# coop_assistant.net
KiCad netlist of a schematic drawn in EAGLE
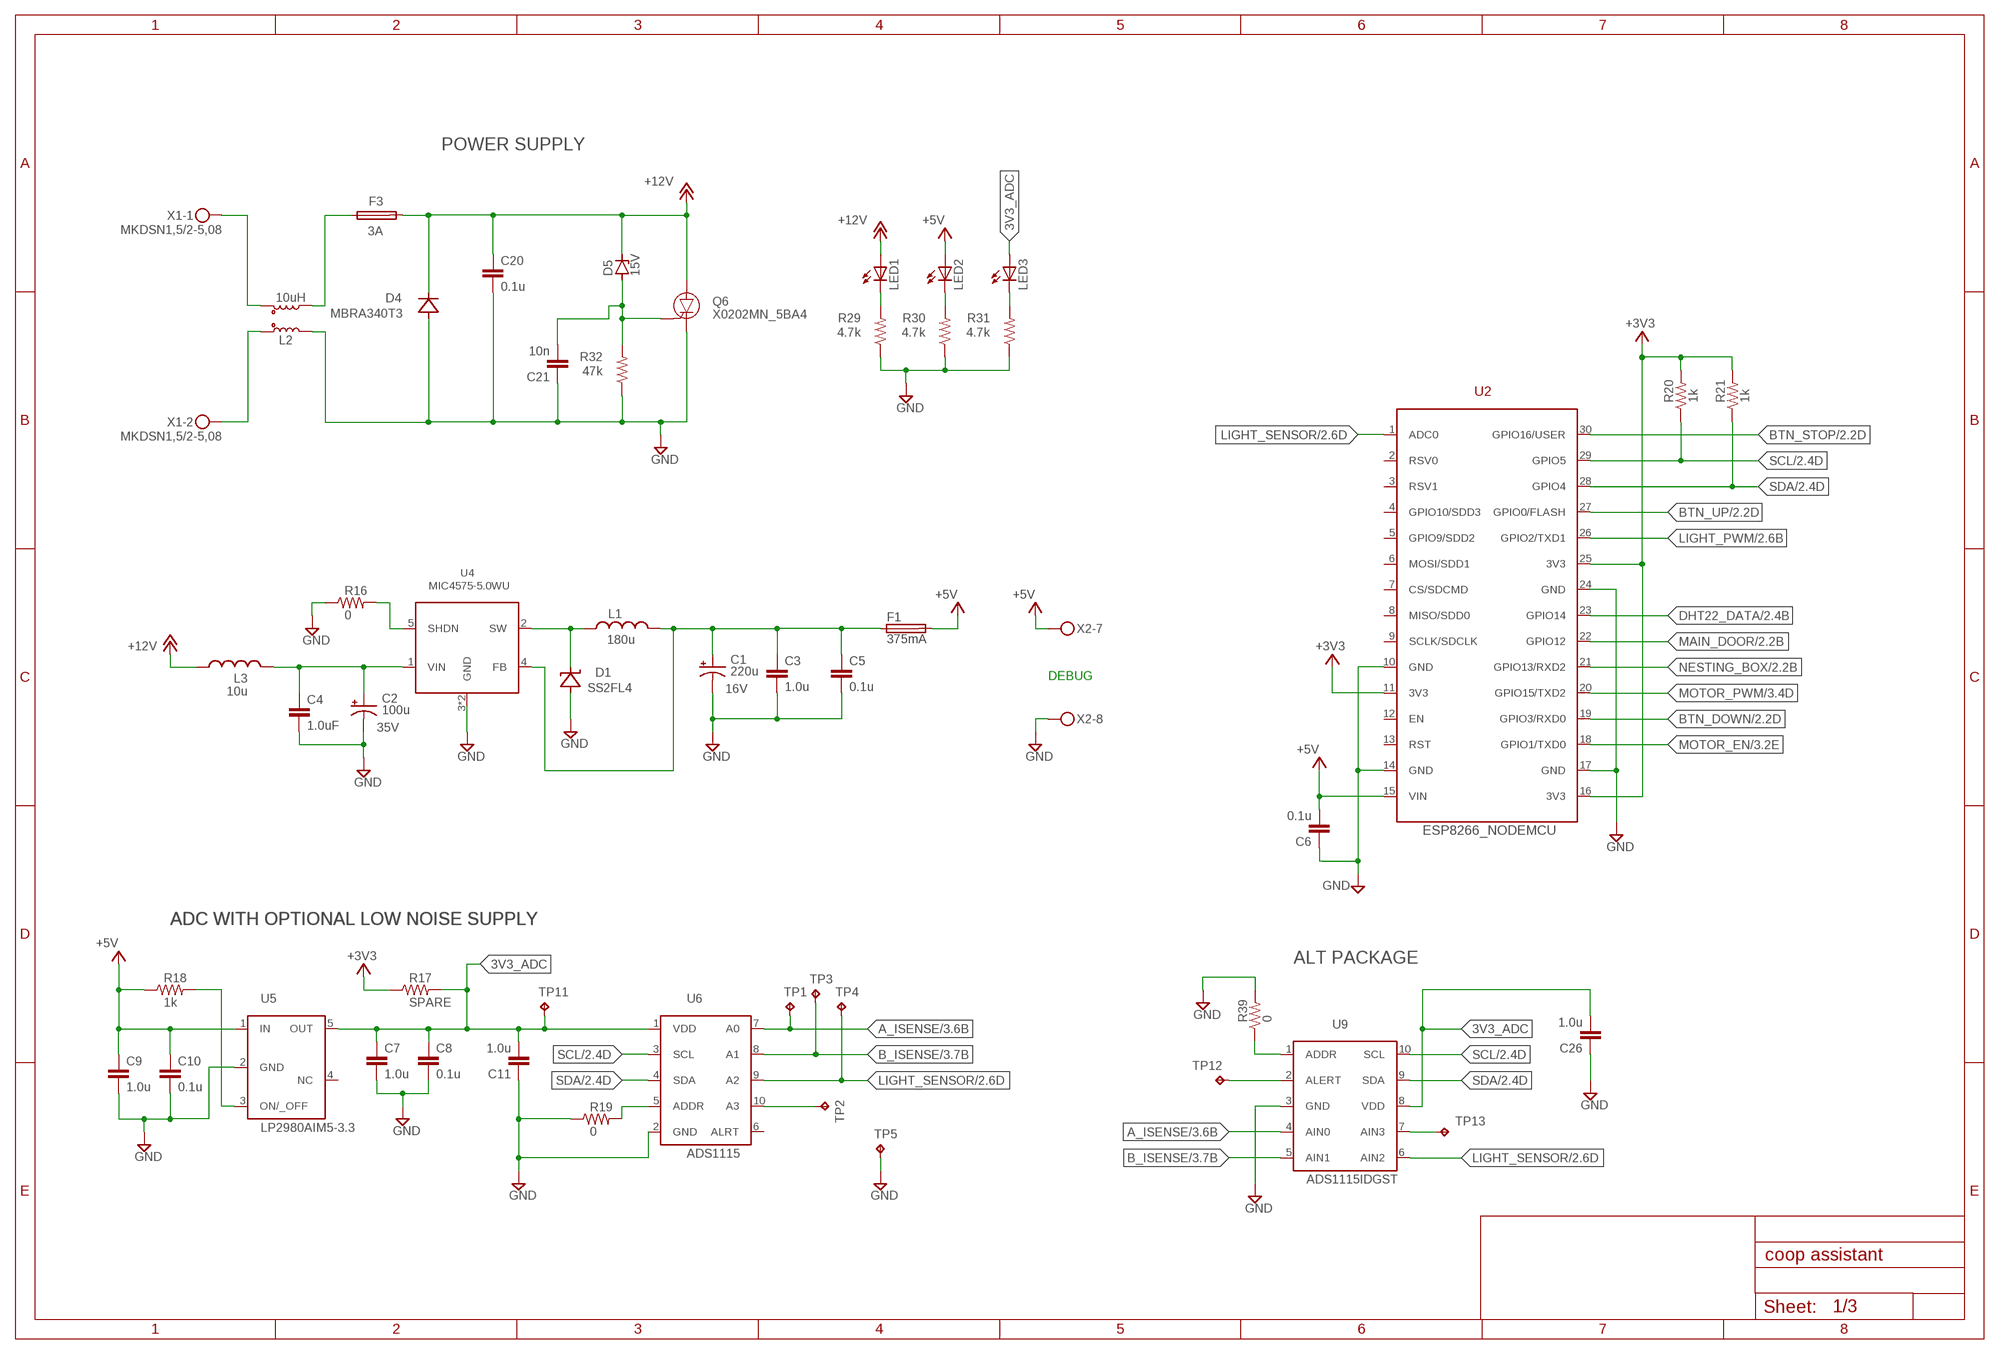
[diagram p0: schematic, sheet 1]
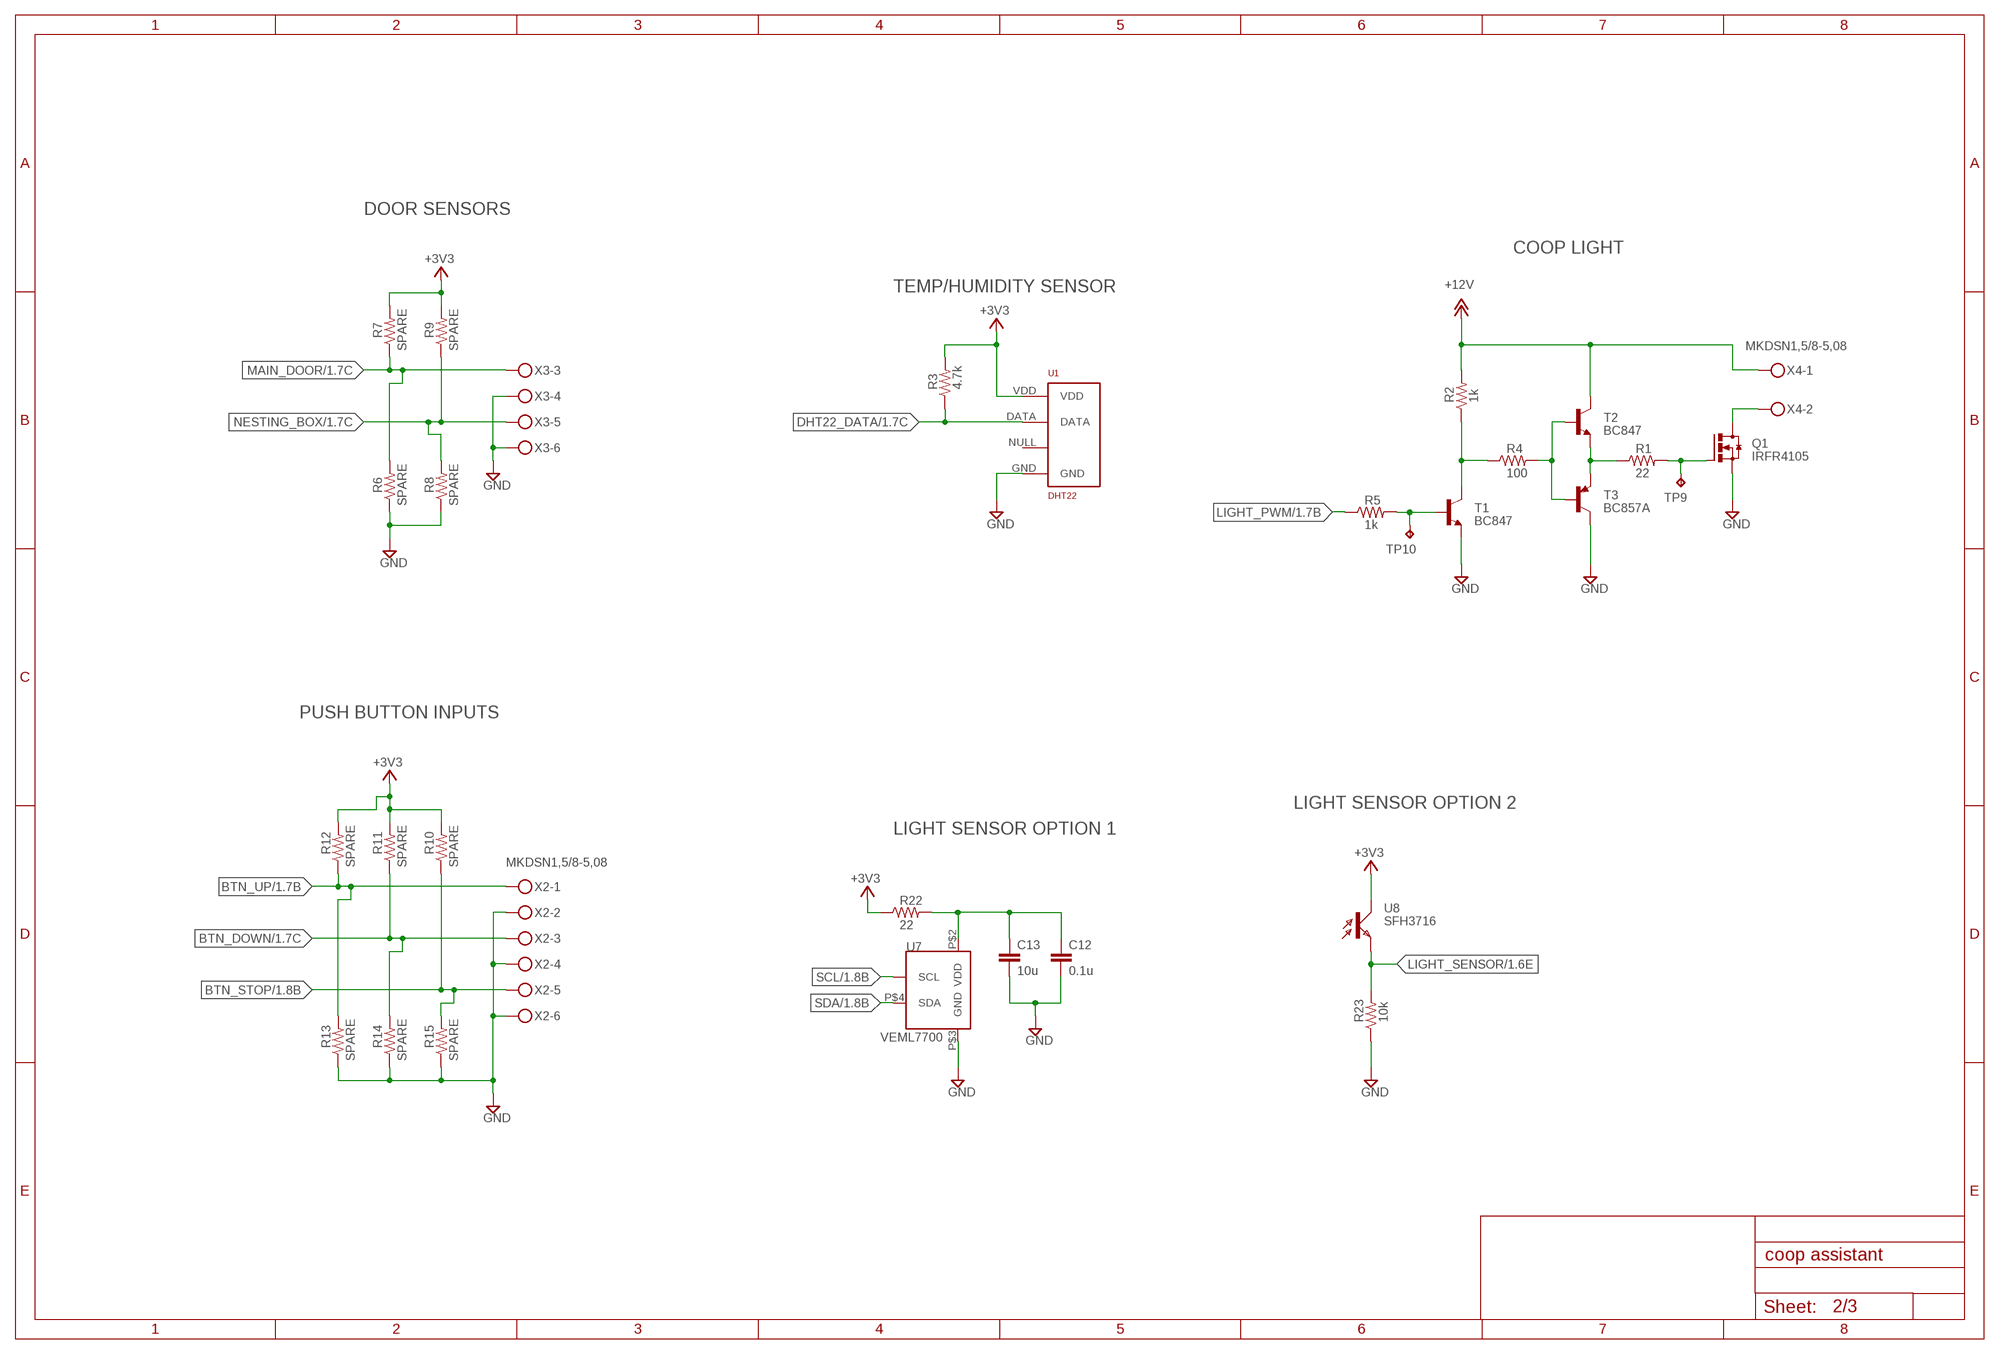
[diagram p1: schematic, sheet 2]
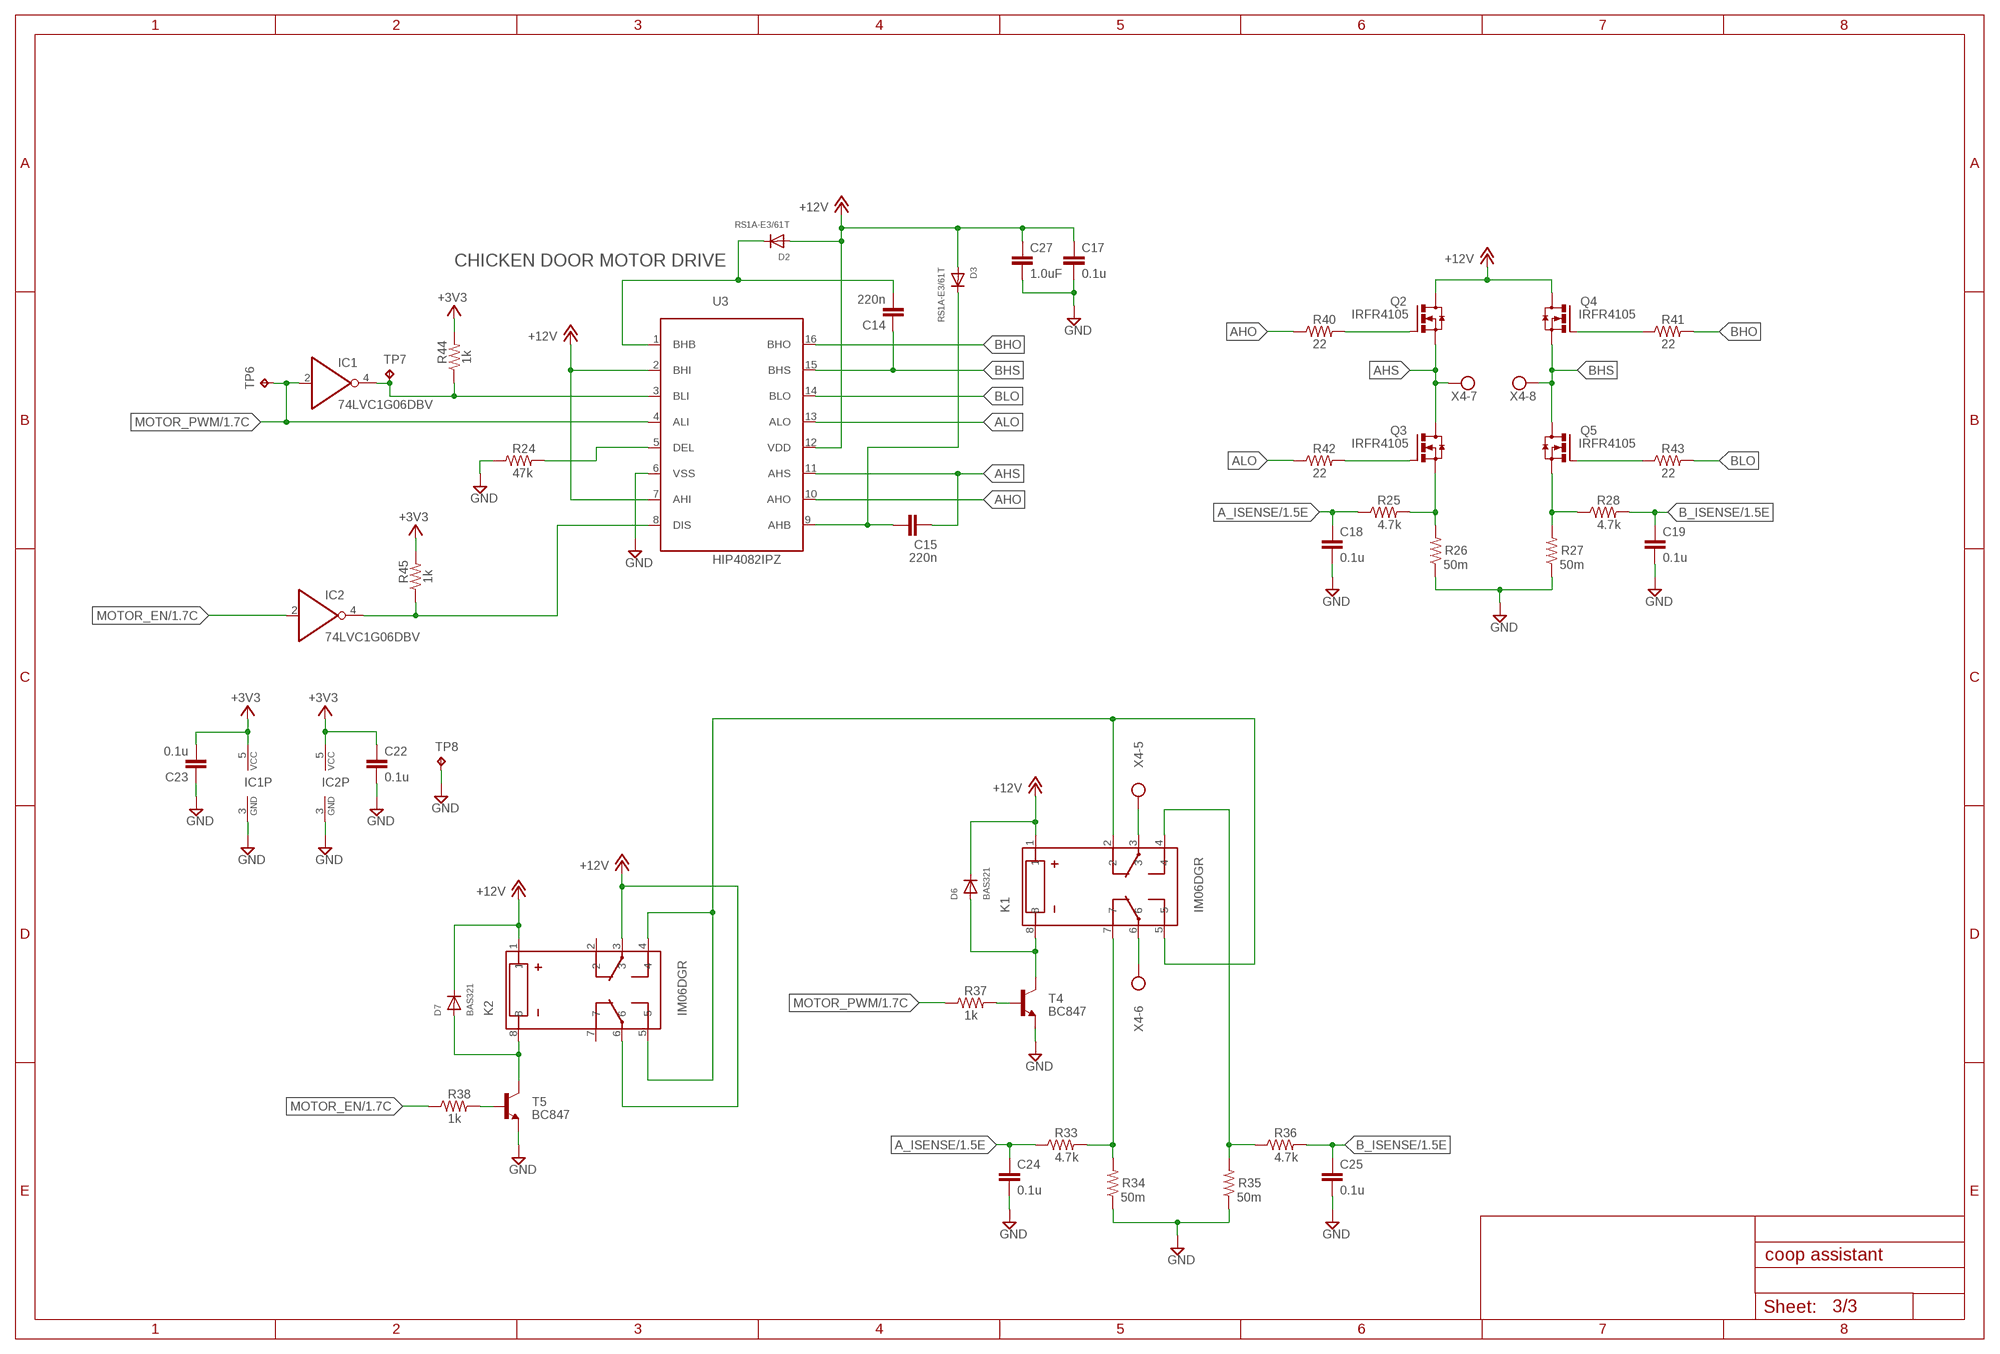
[diagram p2: schematic, sheet 3]

(export (version "E")
  (design (tool "Eeschema 10.0.6"))
  (components
    (comp (ref "C14")
      (value "220n")
      (footprint "eagle-import:0805")
      (libsource (lib "eagle-import") (part "1.0UF-0805-25V-(+80/-20%)"))
    )
    (comp (ref "C15")
      (value "220n")
      (footprint "eagle-import:0805")
      (libsource (lib "eagle-import") (part "1.0UF-0805-25V-(+80/-20%)"))
    )
    (comp (ref "C17")
      (value "0.1u")
      (footprint "eagle-import:0603")
      (libsource (lib "eagle-import") (part "1.0UF-0603-16V-10%"))
    )
    (comp (ref "C18")
      (value "0.1u")
      (footprint "eagle-import:0603")
      (libsource (lib "eagle-import") (part "1.0UF-0603-16V-10%"))
    )
    (comp (ref "C19")
      (value "0.1u")
      (footprint "eagle-import:0603")
      (libsource (lib "eagle-import") (part "1.0UF-0603-16V-10%"))
    )
    (comp (ref "C22")
      (value "0.1u")
      (footprint "eagle-import:0603")
      (libsource (lib "eagle-import") (part "1.0UF-0603-16V-10%"))
    )
    (comp (ref "C23")
      (value "0.1u")
      (footprint "eagle-import:0603")
      (libsource (lib "eagle-import") (part "1.0UF-0603-16V-10%"))
    )
    (comp (ref "C24")
      (value "0.1u")
      (footprint "eagle-import:0603")
      (libsource (lib "eagle-import") (part "1.0UF-0603-16V-10%"))
    )
    (comp (ref "C25")
      (value "0.1u")
      (footprint "eagle-import:0603")
      (libsource (lib "eagle-import") (part "1.0UF-0603-16V-10%"))
    )
    (comp (ref "C27")
      (value "1.0uF")
      (footprint "eagle-import:0805")
      (libsource (lib "eagle-import") (part "1.0UF-0805-25V-10%"))
    )
    (comp (ref "D2")
      (value "RS1A-E3/61T")
      (footprint "eagle-import:SMADIODE")
      (libsource (lib "eagle-import") (part "DIODESMA"))
    )
    (comp (ref "D3")
      (value "RS1A-E3/61T")
      (footprint "eagle-import:SMADIODE")
      (libsource (lib "eagle-import") (part "DIODESMA"))
    )
    (comp (ref "D6")
      (value "BAS321")
      (footprint "eagle-import:SOD-323F")
      (libsource (lib "eagle-import") (part "DIODESOD-323F"))
    )
    (comp (ref "D7")
      (value "BAS321")
      (footprint "eagle-import:SOD-323F")
      (libsource (lib "eagle-import") (part "DIODESOD-323F"))
    )
    (comp (ref "IC1")
      (value "74LVC1G06DBV")
      (footprint "eagle-import:SOT23-5")
      (libsource (lib "eagle-import") (part "741G06DBVLVC"))
    )
    (comp (ref "IC2")
      (value "74LVC1G06DBV")
      (footprint "eagle-import:SOT23-5")
      (libsource (lib "eagle-import") (part "741G06DBVLVC"))
    )
    (comp (ref "K1")
      (value "IM06DGR")
      (footprint "eagle-import:AXICOM_IM")
      (libsource (lib "eagle-import") (part "IM06DGR"))
    )
    (comp (ref "K2")
      (value "IM06DGR")
      (footprint "eagle-import:AXICOM_IM")
      (libsource (lib "eagle-import") (part "IM06DGR"))
    )
    (comp (ref "Q2")
      (value "IRFR4105")
      (footprint "eagle-import:TO252")
      (libsource (lib "eagle-import") (part "IRFR4105"))
    )
    (comp (ref "Q3")
      (value "IRFR4105")
      (footprint "eagle-import:TO252")
      (libsource (lib "eagle-import") (part "IRFR4105"))
    )
    (comp (ref "Q4")
      (value "IRFR4105")
      (footprint "eagle-import:TO252")
      (libsource (lib "eagle-import") (part "IRFR4105"))
    )
    (comp (ref "Q5")
      (value "IRFR4105")
      (footprint "eagle-import:TO252")
      (libsource (lib "eagle-import") (part "IRFR4105"))
    )
    (comp (ref "R24")
      (value "47k")
      (footprint "eagle-import:R0805")
      (libsource (lib "eagle-import") (part "R-US_R0805"))
    )
    (comp (ref "R25")
      (value "4.7k")
      (footprint "eagle-import:R0805")
      (libsource (lib "eagle-import") (part "R-US_R0805"))
    )
    (comp (ref "R26")
      (value "50m")
      (footprint "eagle-import:R2512")
      (libsource (lib "eagle-import") (part "R-US_R2512"))
    )
    (comp (ref "R27")
      (value "50m")
      (footprint "eagle-import:R2512")
      (libsource (lib "eagle-import") (part "R-US_R2512"))
    )
    (comp (ref "R28")
      (value "4.7k")
      (footprint "eagle-import:R0805")
      (libsource (lib "eagle-import") (part "R-US_R0805"))
    )
    (comp (ref "R33")
      (value "4.7k")
      (footprint "eagle-import:R0805")
      (libsource (lib "eagle-import") (part "R-US_R0805"))
    )
    (comp (ref "R34")
      (value "50m")
      (footprint "eagle-import:R2512")
      (libsource (lib "eagle-import") (part "R-US_R2512"))
    )
    (comp (ref "R35")
      (value "50m")
      (footprint "eagle-import:R2512")
      (libsource (lib "eagle-import") (part "R-US_R2512"))
    )
    (comp (ref "R36")
      (value "4.7k")
      (footprint "eagle-import:R0805")
      (libsource (lib "eagle-import") (part "R-US_R0805"))
    )
    (comp (ref "R37")
      (value "1k")
      (footprint "eagle-import:R0805")
      (libsource (lib "eagle-import") (part "R-US_R0805"))
    )
    (comp (ref "R38")
      (value "1k")
      (footprint "eagle-import:R0805")
      (libsource (lib "eagle-import") (part "R-US_R0805"))
    )
    (comp (ref "R40")
      (value "22")
      (footprint "eagle-import:R0805")
      (libsource (lib "eagle-import") (part "R-US_R0805"))
    )
    (comp (ref "R41")
      (value "22")
      (footprint "eagle-import:R0805")
      (libsource (lib "eagle-import") (part "R-US_R0805"))
    )
    (comp (ref "R42")
      (value "22")
      (footprint "eagle-import:R0805")
      (libsource (lib "eagle-import") (part "R-US_R0805"))
    )
    (comp (ref "R43")
      (value "22")
      (footprint "eagle-import:R0805")
      (libsource (lib "eagle-import") (part "R-US_R0805"))
    )
    (comp (ref "R44")
      (value "1k")
      (footprint "eagle-import:R0805")
      (libsource (lib "eagle-import") (part "R-US_R0805"))
    )
    (comp (ref "R45")
      (value "1k")
      (footprint "eagle-import:R0805")
      (libsource (lib "eagle-import") (part "R-US_R0805"))
    )
    (comp (ref "T4")
      (value "BC847")
      (footprint "eagle-import:SOT23")
      (libsource (lib "eagle-import") (part "BC847"))
    )
    (comp (ref "T5")
      (value "BC847")
      (footprint "eagle-import:SOT23")
      (libsource (lib "eagle-import") (part "BC847"))
    )
    (comp (ref "TP6")
      (value "TPTP15SQ")
      (footprint "eagle-import:TP15SQ")
      (libsource (lib "eagle-import") (part "TPTP15SQ"))
    )
    (comp (ref "TP7")
      (value "TPTP15SQ")
      (footprint "eagle-import:TP15SQ")
      (libsource (lib "eagle-import") (part "TPTP15SQ"))
    )
    (comp (ref "TP8")
      (value "TPTP15SQ")
      (footprint "eagle-import:TP15SQ")
      (libsource (lib "eagle-import") (part "TPTP15SQ"))
    )
    (comp (ref "U3")
      (value "HIP4082IPZ")
      (footprint "eagle-import:DIP762W53P254L1969H508Q16B")
      (libsource (lib "eagle-import") (part "HIP4082IPZ"))
    )
    (comp (ref "X4")
      (value "MKDSN1,5/8-5,08")
      (footprint "eagle-import:MKDSN1,5_8-5,08")
      (libsource (lib "eagle-import") (part "MKDSN1,5/8-5,08"))
    )
    (comp (ref "C1")
      (value "220u")
      (footprint "eagle-import:CAPPRD250W50D630H800B")
      (fields (field (name "VOLTAGE") "16V"))
      (libsource (lib "eagle-import") (part "CPOLRAD6.3X8"))
    )
    (comp (ref "C2")
      (value "100u")
      (footprint "eagle-import:CAPPRD350W60D800H1200B")
      (fields (field (name "VOLTAGE") "35V"))
      (libsource (lib "eagle-import") (part "CPOLRAD8X12"))
    )
    (comp (ref "C3")
      (value "1.0u")
      (footprint "eagle-import:0805")
      (libsource (lib "eagle-import") (part "1.0UF-0805-25V-10%"))
    )
    (comp (ref "C4")
      (value "1.0uF")
      (footprint "eagle-import:0805")
      (libsource (lib "eagle-import") (part "1.0UF-0805-25V-10%"))
    )
    (comp (ref "C5")
      (value "0.1u")
      (footprint "eagle-import:0603")
      (libsource (lib "eagle-import") (part "1.0UF-0603-16V-10%"))
    )
    (comp (ref "C6")
      (value "0.1u")
      (footprint "eagle-import:0603")
      (libsource (lib "eagle-import") (part "1.0UF-0603-16V-10%"))
    )
    (comp (ref "C7")
      (value "1.0u")
      (footprint "eagle-import:0805")
      (libsource (lib "eagle-import") (part "1.0UF-0805-25V-10%"))
    )
    (comp (ref "C8")
      (value "0.1u")
      (footprint "eagle-import:0603")
      (libsource (lib "eagle-import") (part "1.0UF-0603-16V-10%"))
    )
    (comp (ref "C9")
      (value "1.0u")
      (footprint "eagle-import:0805")
      (libsource (lib "eagle-import") (part "1.0UF-0805-25V-10%"))
    )
    (comp (ref "C10")
      (value "0.1u")
      (footprint "eagle-import:0603")
      (libsource (lib "eagle-import") (part "1.0UF-0603-16V-10%"))
    )
    (comp (ref "C11")
      (value "1.0u")
      (footprint "eagle-import:0805")
      (libsource (lib "eagle-import") (part "1.0UF-0805-25V-10%"))
    )
    (comp (ref "C20")
      (value "0.1u")
      (footprint "eagle-import:C0805")
      (libsource (lib "eagle-import") (part "C-EUC0805"))
    )
    (comp (ref "C21")
      (value "10n")
      (footprint "eagle-import:C0805")
      (libsource (lib "eagle-import") (part "C-EUC0805"))
    )
    (comp (ref "C26")
      (value "1.0u")
      (footprint "eagle-import:0805")
      (libsource (lib "eagle-import") (part "1.0UF-0805-25V-10%"))
    )
    (comp (ref "D1")
      (value "SS2FL4")
      (footprint "eagle-import:SMF")
      (libsource (lib "eagle-import") (part "SS2FL4"))
    )
    (comp (ref "D4")
      (value "MBRA340T3")
      (footprint "eagle-import:SMA")
      (libsource (lib "eagle-import") (part "MBRA340T3"))
    )
    (comp (ref "D5")
      (value "15V")
      (footprint "eagle-import:SOT23")
      (libsource (lib "eagle-import") (part "ZENER-DIODESOT23"))
    )
    (comp (ref "F1")
      (value "375mA")
      (footprint "eagle-import:0603")
      (libsource (lib "eagle-import") (part "494SERIESFUSE"))
    )
    (comp (ref "F3")
      (value "3A")
      (footprint "eagle-import:FUSM9750X381N")
      (libsource (lib "eagle-import") (part "154_OMNIBLOKF154"))
    )
    (comp (ref "L1")
      (value "180u")
      (footprint "eagle-import:INDM120120X780N")
      (libsource (lib "eagle-import") (part "MSS1278"))
    )
    (comp (ref "L2")
      (value "10uH")
      (footprint "eagle-import:COILCRAFT_MSD1260")
      (libsource (lib "eagle-import") (part "COILCRAFT_MSD1260"))
    )
    (comp (ref "L3")
      (value "10u")
      (footprint "eagle-import:INDM120120X780N")
      (libsource (lib "eagle-import") (part "MSS1278"))
    )
    (comp (ref "LED1")
      (value "LEDCHIP-LED0805")
      (footprint "eagle-import:CHIP-LED0805")
      (libsource (lib "eagle-import") (part "LEDCHIP-LED0805"))
    )
    (comp (ref "LED2")
      (value "LEDCHIP-LED0805")
      (footprint "eagle-import:CHIP-LED0805")
      (libsource (lib "eagle-import") (part "LEDCHIP-LED0805"))
    )
    (comp (ref "LED3")
      (value "LEDCHIP-LED0805")
      (footprint "eagle-import:CHIP-LED0805")
      (libsource (lib "eagle-import") (part "LEDCHIP-LED0805"))
    )
    (comp (ref "Q6")
      (value "X0202MN_5BA4")
      (footprint "eagle-import:SOT-223")
      (fields
        (field (name "DIGIKEY_PARTNO") "497-2532-2-ND")
        (field (name "MANUFACTURER") "STMicroelectronics")
        (field (name "MPN") "X0202MN 5BA4")
        (field (name "CREATED_BY") "PCBLayout.com")
      )
      (libsource (lib "eagle-import") (part "X0202MN_5BA4"))
    )
    (comp (ref "R16")
      (value "0")
      (footprint "eagle-import:R0805")
      (libsource (lib "eagle-import") (part "R-US_R0805"))
    )
    (comp (ref "R17")
      (value "SPARE")
      (footprint "eagle-import:R0805")
      (libsource (lib "eagle-import") (part "R-US_R0805"))
    )
    (comp (ref "R18")
      (value "1k")
      (footprint "eagle-import:R0805")
      (libsource (lib "eagle-import") (part "R-US_R0805"))
    )
    (comp (ref "R19")
      (value "0")
      (footprint "eagle-import:R0805")
      (libsource (lib "eagle-import") (part "R-US_R0805"))
    )
    (comp (ref "R20")
      (value "1k")
      (footprint "eagle-import:R0805")
      (libsource (lib "eagle-import") (part "R-US_R0805"))
    )
    (comp (ref "R21")
      (value "1k")
      (footprint "eagle-import:R0805")
      (libsource (lib "eagle-import") (part "R-US_R0805"))
    )
    (comp (ref "R29")
      (value "4.7k")
      (footprint "eagle-import:R0805")
      (libsource (lib "eagle-import") (part "R-US_R0805"))
    )
    (comp (ref "R30")
      (value "4.7k")
      (footprint "eagle-import:R0805")
      (libsource (lib "eagle-import") (part "R-US_R0805"))
    )
    (comp (ref "R31")
      (value "4.7k")
      (footprint "eagle-import:R0805")
      (libsource (lib "eagle-import") (part "R-US_R0805"))
    )
    (comp (ref "R32")
      (value "47k")
      (footprint "eagle-import:R0805")
      (libsource (lib "eagle-import") (part "R-US_R0805"))
    )
    (comp (ref "R39")
      (value "0")
      (footprint "eagle-import:R0805")
      (libsource (lib "eagle-import") (part "R-US_R0805"))
    )
    (comp (ref "TP1")
      (value "TPTP15SQ")
      (footprint "eagle-import:TP15SQ")
      (libsource (lib "eagle-import") (part "TPTP15SQ"))
    )
    (comp (ref "TP2")
      (value "TPTP15SQ")
      (footprint "eagle-import:TP15SQ")
      (libsource (lib "eagle-import") (part "TPTP15SQ"))
    )
    (comp (ref "TP3")
      (value "TPTP15SQ")
      (footprint "eagle-import:TP15SQ")
      (libsource (lib "eagle-import") (part "TPTP15SQ"))
    )
    (comp (ref "TP4")
      (value "TPTP15SQ")
      (footprint "eagle-import:TP15SQ")
      (libsource (lib "eagle-import") (part "TPTP15SQ"))
    )
    (comp (ref "TP5")
      (value "TPTP15SQ")
      (footprint "eagle-import:TP15SQ")
      (libsource (lib "eagle-import") (part "TPTP15SQ"))
    )
    (comp (ref "TP11")
      (value "TPTP15SQ")
      (footprint "eagle-import:TP15SQ")
      (libsource (lib "eagle-import") (part "TPTP15SQ"))
    )
    (comp (ref "TP12")
      (value "TPTP15SQ")
      (footprint "eagle-import:TP15SQ")
      (libsource (lib "eagle-import") (part "TPTP15SQ"))
    )
    (comp (ref "TP13")
      (value "TPTP15SQ")
      (footprint "eagle-import:TP15SQ")
      (libsource (lib "eagle-import") (part "TPTP15SQ"))
    )
    (comp (ref "U2")
      (value "ESP8266_NODEMCU")
      (footprint "eagle-import:NODEMCUESP8266")
      (libsource (lib "eagle-import") (part "ESP8266_NODEMCU"))
    )
    (comp (ref "U4")
      (value "MIC4575-5.0WU")
      (footprint "eagle-import:TO263-5")
      (libsource (lib "eagle-import") (part "MIC4575-5.0WU"))
    )
    (comp (ref "U5")
      (value "LP2980AIM5-3.3")
      (footprint "eagle-import:SOT23-5")
      (libsource (lib "eagle-import") (part "LP2980AIM5-3.3"))
    )
    (comp (ref "U6")
      (value "ADS1115")
      (footprint "eagle-import:HDRV10W64P254_1X10_2800X508X838B")
      (libsource (lib "eagle-import") (part "ADS1115"))
    )
    (comp (ref "U9")
      (value "ADS1115IDGST")
      (footprint "eagle-import:10VSSOP")
      (libsource (lib "eagle-import") (part "ADS1115IDGST"))
    )
    (comp (ref "X1")
      (value "MKDSN1,5/2-5,08")
      (footprint "eagle-import:MKDSN1,5_2-5,08")
      (libsource (lib "eagle-import") (part "MKDSN1,5/2-5,08"))
    )
    (comp (ref "X2")
      (value "MKDSN1,5/8-5,08")
      (footprint "eagle-import:MKDSN1,5_8-5,08")
      (libsource (lib "eagle-import") (part "MKDSN1,5/8-5,08"))
    )
    (comp (ref "C12")
      (value "0.1u")
      (footprint "eagle-import:0603")
      (libsource (lib "eagle-import") (part "1.0UF-0603-16V-10%"))
    )
    (comp (ref "C13")
      (value "10u")
      (footprint "eagle-import:0805")
      (libsource (lib "eagle-import") (part "1.0UF-0805-25V-(+80/-20%)"))
    )
    (comp (ref "Q1")
      (value "IRFR4105")
      (footprint "eagle-import:TO252")
      (libsource (lib "eagle-import") (part "IRFR4105"))
    )
    (comp (ref "R1")
      (value "22")
      (footprint "eagle-import:R0805")
      (libsource (lib "eagle-import") (part "R-US_R0805"))
    )
    (comp (ref "R2")
      (value "1k")
      (footprint "eagle-import:R0805")
      (libsource (lib "eagle-import") (part "R-US_R0805"))
    )
    (comp (ref "R3")
      (value "4.7k")
      (footprint "eagle-import:R0805")
      (libsource (lib "eagle-import") (part "R-US_R0805"))
    )
    (comp (ref "R4")
      (value "100")
      (footprint "eagle-import:R0805")
      (libsource (lib "eagle-import") (part "R-US_R0805"))
    )
    (comp (ref "R5")
      (value "1k")
      (footprint "eagle-import:R0805")
      (libsource (lib "eagle-import") (part "R-US_R0805"))
    )
    (comp (ref "R6")
      (value "SPARE")
      (footprint "eagle-import:R0805")
      (libsource (lib "eagle-import") (part "R-US_R0805"))
    )
    (comp (ref "R7")
      (value "SPARE")
      (footprint "eagle-import:R0805")
      (libsource (lib "eagle-import") (part "R-US_R0805"))
    )
    (comp (ref "R8")
      (value "SPARE")
      (footprint "eagle-import:R0805")
      (libsource (lib "eagle-import") (part "R-US_R0805"))
    )
    (comp (ref "R9")
      (value "SPARE")
      (footprint "eagle-import:R0805")
      (libsource (lib "eagle-import") (part "R-US_R0805"))
    )
    (comp (ref "R10")
      (value "SPARE")
      (footprint "eagle-import:R0805")
      (libsource (lib "eagle-import") (part "R-US_R0805"))
    )
    (comp (ref "R11")
      (value "SPARE")
      (footprint "eagle-import:R0805")
      (libsource (lib "eagle-import") (part "R-US_R0805"))
    )
    (comp (ref "R12")
      (value "SPARE")
      (footprint "eagle-import:R0805")
      (libsource (lib "eagle-import") (part "R-US_R0805"))
    )
    (comp (ref "R13")
      (value "SPARE")
      (footprint "eagle-import:R0805")
      (libsource (lib "eagle-import") (part "R-US_R0805"))
    )
    (comp (ref "R14")
      (value "SPARE")
      (footprint "eagle-import:R0805")
      (libsource (lib "eagle-import") (part "R-US_R0805"))
    )
    (comp (ref "R15")
      (value "SPARE")
      (footprint "eagle-import:R0805")
      (libsource (lib "eagle-import") (part "R-US_R0805"))
    )
    (comp (ref "R22")
      (value "22")
      (footprint "eagle-import:R0805")
      (libsource (lib "eagle-import") (part "R-US_R0805"))
    )
    (comp (ref "R23")
      (value "10k")
      (footprint "eagle-import:R0805")
      (libsource (lib "eagle-import") (part "R-US_R0805"))
    )
    (comp (ref "T1")
      (value "BC847")
      (footprint "eagle-import:SOT23")
      (libsource (lib "eagle-import") (part "BC847"))
    )
    (comp (ref "T2")
      (value "BC847")
      (footprint "eagle-import:SOT23")
      (libsource (lib "eagle-import") (part "BC847"))
    )
    (comp (ref "T3")
      (value "BC857A")
      (footprint "eagle-import:SOT23-BEC")
      (libsource (lib "eagle-import") (part "BC857A"))
    )
    (comp (ref "TP9")
      (value "TPTP15SQ")
      (footprint "eagle-import:TP15SQ")
      (libsource (lib "eagle-import") (part "TPTP15SQ"))
    )
    (comp (ref "TP10")
      (value "TPTP15SQ")
      (footprint "eagle-import:TP15SQ")
      (libsource (lib "eagle-import") (part "TPTP15SQ"))
    )
    (comp (ref "U1")
      (value "DHT22")
      (footprint "eagle-import:RHT03_DHT-22_RA")
      (libsource (lib "eagle-import") (part "RHT03_DHT-22_AM2302RA"))
    )
    (comp (ref "U7")
      (value "VEML7700")
      (footprint "eagle-import:VEML7700")
      (libsource (lib "eagle-import") (part "VEML7700"))
    )
    (comp (ref "U8")
      (value "SFH3716")
      (footprint "eagle-import:0805")
      (libsource (lib "eagle-import") (part "SFH3716"))
    )
    (comp (ref "X3")
      (value "MKDSN1,5/8-5,08")
      (footprint "eagle-import:MKDSN1,5_8-5,08")
      (libsource (lib "eagle-import") (part "MKDSN1,5/8-5,08"))
    )
  )
  (nets
    (net (code "1") (name "+3V3") (class "Default")
      (node (ref "C22") (pin "1") (pinfunction "1_1") (pintype "passive"))
      (node (ref "C23") (pin "2") (pinfunction "2_2") (pintype "passive"))
      (node (ref "IC1") (pin "5") (pinfunction "VCC_5") (pintype "power_in"))
      (node (ref "IC2") (pin "5") (pinfunction "VCC_5") (pintype "power_in"))
      (node (ref "R10") (pin "2") (pinfunction "2_2") (pintype "passive"))
      (node (ref "R11") (pin "2") (pinfunction "2_2") (pintype "passive"))
      (node (ref "R12") (pin "2") (pinfunction "2_2") (pintype "passive"))
      (node (ref "R17") (pin "1") (pinfunction "1_1") (pintype "passive"))
      (node (ref "R20") (pin "2") (pinfunction "2_2") (pintype "passive"))
      (node (ref "R21") (pin "2") (pinfunction "2_2") (pintype "passive"))
      (node (ref "R22") (pin "1") (pinfunction "1_1") (pintype "passive"))
      (node (ref "R3") (pin "2") (pinfunction "2_2") (pintype "passive"))
      (node (ref "R44") (pin "2") (pinfunction "2_2") (pintype "passive"))
      (node (ref "R45") (pin "2") (pinfunction "2_2") (pintype "passive"))
      (node (ref "R7") (pin "2") (pinfunction "2_2") (pintype "passive"))
      (node (ref "R9") (pin "2") (pinfunction "2_2") (pintype "passive"))
      (node (ref "U1") (pin "VDD") (pinfunction "VDD_VDD") (pintype "power_in"))
      (node (ref "U2") (pin "11") (pinfunction "3V3_11") (pintype "power_in"))
      (node (ref "U2") (pin "16") (pinfunction "3V3_16") (pintype "power_in"))
      (node (ref "U2") (pin "25") (pinfunction "3V3_25") (pintype "power_in"))
      (node (ref "U8") (pin "1") (pinfunction "C_1") (pintype "passive"))
    )
    (net (code "2") (name "+5V") (class "Default")
      (node (ref "C10") (pin "1") (pinfunction "1_1") (pintype "passive"))
      (node (ref "C6") (pin "2") (pinfunction "2_2") (pintype "passive"))
      (node (ref "C9") (pin "1") (pinfunction "1_1") (pintype "passive"))
      (node (ref "F1") (pin "2") (pinfunction "2_2") (pintype "passive"))
      (node (ref "LED2") (pin "A") (pinfunction "A_A") (pintype "passive"))
      (node (ref "R18") (pin "1") (pinfunction "1_1") (pintype "passive"))
      (node (ref "U2") (pin "15") (pinfunction "VIN_15") (pintype "power_in"))
      (node (ref "U5") (pin "1") (pinfunction "IN_1") (pintype "power_in"))
      (node (ref "X2") (pin "7") (pinfunction "KL_7") (pintype "passive"))
    )
    (net (code "3") (name "+12V") (class "Default")
      (node (ref "C17") (pin "1") (pinfunction "1_1") (pintype "passive"))
      (node (ref "C20") (pin "1") (pinfunction "1_1") (pintype "passive"))
      (node (ref "C27") (pin "1") (pinfunction "1_1") (pintype "passive"))
      (node (ref "D2") (pin "A") (pinfunction "A_A") (pintype "passive"))
      (node (ref "D3") (pin "A") (pinfunction "A_A") (pintype "passive"))
      (node (ref "D4") (pin "C") (pinfunction "C_C") (pintype "passive"))
      (node (ref "D5") (pin "3") (pinfunction "C_3") (pintype "passive"))
      (node (ref "D6") (pin "C") (pinfunction "C_C") (pintype "passive"))
      (node (ref "D7") (pin "C") (pinfunction "C_C") (pintype "passive"))
      (node (ref "F3") (pin "2") (pinfunction "2_2") (pintype "passive"))
      (node (ref "K1") (pin "1") (pinfunction "1_1") (pintype "bidirectional"))
      (node (ref "K2") (pin "1") (pinfunction "1_1") (pintype "bidirectional"))
      (node (ref "K2") (pin "3") (pinfunction "3_3") (pintype "bidirectional"))
      (node (ref "K2") (pin "6") (pinfunction "6_6") (pintype "bidirectional"))
      (node (ref "L3") (pin "1") (pinfunction "1_1") (pintype "passive"))
      (node (ref "LED1") (pin "A") (pinfunction "A_A") (pintype "passive"))
      (node (ref "Q2") (pin "3") (pinfunction "D_3") (pintype "passive"))
      (node (ref "Q4") (pin "3") (pinfunction "D_3") (pintype "passive"))
      (node (ref "Q6") (pin "A") (pinfunction "A_A") (pintype "passive"))
      (node (ref "Q6") (pin "A1") (pinfunction "A_A1") (pintype "passive"))
      (node (ref "R2") (pin "2") (pinfunction "2_2") (pintype "passive"))
      (node (ref "T2") (pin "3") (pinfunction "C_3") (pintype "passive"))
      (node (ref "U3") (pin "12") (pinfunction "VDD_12") (pintype "power_in"))
      (node (ref "U3") (pin "2") (pinfunction "BHI_2") (pintype "bidirectional"))
      (node (ref "U3") (pin "7") (pinfunction "AHI_7") (pintype "bidirectional"))
      (node (ref "X4") (pin "1") (pinfunction "KL_1") (pintype "passive"))
    )
    (net (code "4") (name "3V3_ADC") (class "Default")
      (node (ref "C11") (pin "2") (pinfunction "2_2") (pintype "passive"))
      (node (ref "C26") (pin "2") (pinfunction "2_2") (pintype "passive"))
      (node (ref "C7") (pin "1") (pinfunction "1_1") (pintype "passive"))
      (node (ref "C8") (pin "1") (pinfunction "1_1") (pintype "passive"))
      (node (ref "LED3") (pin "A") (pinfunction "A_A") (pintype "passive"))
      (node (ref "R17") (pin "2") (pinfunction "2_2") (pintype "passive"))
      (node (ref "TP11") (pin "TP") (pinfunction "TP_TP") (pintype "input"))
      (node (ref "U5") (pin "5") (pinfunction "OUT_5") (pintype "power_in"))
      (node (ref "U6") (pin "1") (pinfunction "VDD_1") (pintype "power_in"))
      (node (ref "U9") (pin "8") (pinfunction "VDD_8") (pintype "power_in"))
    )
    (net (code "5") (name "AHO") (class "Default")
      (node (ref "R40") (pin "1") (pinfunction "1_1") (pintype "passive"))
      (node (ref "U3") (pin "10") (pinfunction "AHO_10") (pintype "bidirectional"))
    )
    (net (code "6") (name "AHS") (class "Default")
      (node (ref "C15") (pin "2") (pinfunction "2_2") (pintype "passive"))
      (node (ref "Q2") (pin "2") (pinfunction "S_2") (pintype "passive"))
      (node (ref "Q3") (pin "3") (pinfunction "D_3") (pintype "passive"))
      (node (ref "U3") (pin "11") (pinfunction "AHS_11") (pintype "bidirectional"))
      (node (ref "X4") (pin "7") (pinfunction "KL_7") (pintype "passive"))
    )
    (net (code "7") (name "ALO") (class "Default")
      (node (ref "R42") (pin "1") (pinfunction "1_1") (pintype "passive"))
      (node (ref "U3") (pin "13") (pinfunction "ALO_13") (pintype "bidirectional"))
    )
    (net (code "8") (name "A_ISENSE") (class "Default")
      (node (ref "C18") (pin "1") (pinfunction "1_1") (pintype "passive"))
      (node (ref "C24") (pin "1") (pinfunction "1_1") (pintype "passive"))
      (node (ref "R25") (pin "1") (pinfunction "1_1") (pintype "passive"))
      (node (ref "R33") (pin "1") (pinfunction "1_1") (pintype "passive"))
      (node (ref "TP1") (pin "TP") (pinfunction "TP_TP") (pintype "input"))
      (node (ref "U6") (pin "7") (pinfunction "A0_7") (pintype "input"))
      (node (ref "U9") (pin "4") (pinfunction "AIN0_4") (pintype "input"))
    )
    (net (code "9") (name "BHO") (class "Default")
      (node (ref "R41") (pin "2") (pinfunction "2_2") (pintype "passive"))
      (node (ref "U3") (pin "16") (pinfunction "BHO_16") (pintype "bidirectional"))
    )
    (net (code "10") (name "BHS") (class "Default")
      (node (ref "C14") (pin "1") (pinfunction "1_1") (pintype "passive"))
      (node (ref "Q4") (pin "2") (pinfunction "S_2") (pintype "passive"))
      (node (ref "Q5") (pin "3") (pinfunction "D_3") (pintype "passive"))
      (node (ref "U3") (pin "15") (pinfunction "BHS_15") (pintype "bidirectional"))
      (node (ref "X4") (pin "8") (pinfunction "KL_8") (pintype "passive"))
    )
    (net (code "11") (name "BLO") (class "Default")
      (node (ref "R43") (pin "2") (pinfunction "2_2") (pintype "passive"))
      (node (ref "U3") (pin "14") (pinfunction "BLO_14") (pintype "bidirectional"))
    )
    (net (code "12") (name "BTN_DOWN") (class "Default")
      (node (ref "R11") (pin "1") (pinfunction "1_1") (pintype "passive"))
      (node (ref "R14") (pin "2") (pinfunction "2_2") (pintype "passive"))
      (node (ref "U2") (pin "19") (pinfunction "GPIO3/RXD0_19") (pintype "bidirectional"))
      (node (ref "X2") (pin "3") (pinfunction "KL_3") (pintype "passive"))
    )
    (net (code "13") (name "BTN_STOP") (class "Default")
      (node (ref "R10") (pin "1") (pinfunction "1_1") (pintype "passive"))
      (node (ref "R15") (pin "2") (pinfunction "2_2") (pintype "passive"))
      (node (ref "U2") (pin "30") (pinfunction "GPIO16/USER_30") (pintype "bidirectional"))
      (node (ref "X2") (pin "5") (pinfunction "KL_5") (pintype "passive"))
    )
    (net (code "14") (name "BTN_UP") (class "Default")
      (node (ref "R12") (pin "1") (pinfunction "1_1") (pintype "passive"))
      (node (ref "R13") (pin "2") (pinfunction "2_2") (pintype "passive"))
      (node (ref "U2") (pin "27") (pinfunction "GPIO0/FLASH_27") (pintype "bidirectional"))
      (node (ref "X2") (pin "1") (pinfunction "KL_1") (pintype "passive"))
    )
    (net (code "15") (name "B_ISENSE") (class "Default")
      (node (ref "C19") (pin "1") (pinfunction "1_1") (pintype "passive"))
      (node (ref "C25") (pin "1") (pinfunction "1_1") (pintype "passive"))
      (node (ref "R28") (pin "2") (pinfunction "2_2") (pintype "passive"))
      (node (ref "R36") (pin "2") (pinfunction "2_2") (pintype "passive"))
      (node (ref "TP3") (pin "TP") (pinfunction "TP_TP") (pintype "input"))
      (node (ref "U6") (pin "8") (pinfunction "A1_8") (pintype "input"))
      (node (ref "U9") (pin "5") (pinfunction "AIN1_5") (pintype "input"))
    )
    (net (code "16") (name "DHT22_DATA") (class "Default")
      (node (ref "R3") (pin "1") (pinfunction "1_1") (pintype "passive"))
      (node (ref "U1") (pin "DATA") (pinfunction "DATA_DATA") (pintype "bidirectional"))
      (node (ref "U2") (pin "23") (pinfunction "GPIO14_23") (pintype "bidirectional"))
    )
    (net (code "17") (name "GND") (class "Default")
      (node (ref "C1") (pin "NEG") (pinfunction "-_NEG") (pintype "passive"))
      (node (ref "C10") (pin "2") (pinfunction "2_2") (pintype "passive"))
      (node (ref "C11") (pin "1") (pinfunction "1_1") (pintype "passive"))
      (node (ref "C12") (pin "2") (pinfunction "2_2") (pintype "passive"))
      (node (ref "C13") (pin "2") (pinfunction "2_2") (pintype "passive"))
      (node (ref "C17") (pin "2") (pinfunction "2_2") (pintype "passive"))
      (node (ref "C18") (pin "2") (pinfunction "2_2") (pintype "passive"))
      (node (ref "C19") (pin "2") (pinfunction "2_2") (pintype "passive"))
      (node (ref "C2") (pin "NEG") (pinfunction "-_NEG") (pintype "passive"))
      (node (ref "C20") (pin "2") (pinfunction "2_2") (pintype "passive"))
      (node (ref "C21") (pin "1") (pinfunction "1_1") (pintype "passive"))
      (node (ref "C22") (pin "2") (pinfunction "2_2") (pintype "passive"))
      (node (ref "C23") (pin "1") (pinfunction "1_1") (pintype "passive"))
      (node (ref "C24") (pin "2") (pinfunction "2_2") (pintype "passive"))
      (node (ref "C25") (pin "2") (pinfunction "2_2") (pintype "passive"))
      (node (ref "C26") (pin "1") (pinfunction "1_1") (pintype "passive"))
      (node (ref "C27") (pin "2") (pinfunction "2_2") (pintype "passive"))
      (node (ref "C3") (pin "2") (pinfunction "2_2") (pintype "passive"))
      (node (ref "C4") (pin "2") (pinfunction "2_2") (pintype "passive"))
      (node (ref "C5") (pin "2") (pinfunction "2_2") (pintype "passive"))
      (node (ref "C6") (pin "1") (pinfunction "1_1") (pintype "passive"))
      (node (ref "C7") (pin "2") (pinfunction "2_2") (pintype "passive"))
      (node (ref "C8") (pin "2") (pinfunction "2_2") (pintype "passive"))
      (node (ref "C9") (pin "2") (pinfunction "2_2") (pintype "passive"))
      (node (ref "D1") (pin "A") (pinfunction "A_A") (pintype "passive"))
      (node (ref "D4") (pin "A") (pinfunction "A_A") (pintype "passive"))
      (node (ref "IC1") (pin "3") (pinfunction "GND_3") (pintype "power_in"))
      (node (ref "IC2") (pin "3") (pinfunction "GND_3") (pintype "power_in"))
      (node (ref "L2") (pin "4") (pinfunction "4_4") (pintype "passive"))
      (node (ref "Q1") (pin "2") (pinfunction "S_2") (pintype "passive"))
      (node (ref "Q6") (pin "K") (pinfunction "K_K") (pintype "passive"))
      (node (ref "R13") (pin "1") (pinfunction "1_1") (pintype "passive"))
      (node (ref "R14") (pin "1") (pinfunction "1_1") (pintype "passive"))
      (node (ref "R15") (pin "1") (pinfunction "1_1") (pintype "passive"))
      (node (ref "R16") (pin "1") (pinfunction "1_1") (pintype "passive"))
      (node (ref "R19") (pin "1") (pinfunction "1_1") (pintype "passive"))
      (node (ref "R23") (pin "1") (pinfunction "1_1") (pintype "passive"))
      (node (ref "R24") (pin "1") (pinfunction "1_1") (pintype "passive"))
      (node (ref "R26") (pin "1") (pinfunction "1_1") (pintype "passive"))
      (node (ref "R27") (pin "1") (pinfunction "1_1") (pintype "passive"))
      (node (ref "R29") (pin "1") (pinfunction "1_1") (pintype "passive"))
      (node (ref "R30") (pin "1") (pinfunction "1_1") (pintype "passive"))
      (node (ref "R31") (pin "1") (pinfunction "1_1") (pintype "passive"))
      (node (ref "R32") (pin "1") (pinfunction "1_1") (pintype "passive"))
      (node (ref "R34") (pin "1") (pinfunction "1_1") (pintype "passive"))
      (node (ref "R35") (pin "1") (pinfunction "1_1") (pintype "passive"))
      (node (ref "R39") (pin "2") (pinfunction "2_2") (pintype "passive"))
      (node (ref "R6") (pin "1") (pinfunction "1_1") (pintype "passive"))
      (node (ref "R8") (pin "1") (pinfunction "1_1") (pintype "passive"))
      (node (ref "T1") (pin "2") (pinfunction "E_2") (pintype "passive"))
      (node (ref "T3") (pin "C") (pinfunction "C_C") (pintype "passive"))
      (node (ref "T4") (pin "2") (pinfunction "E_2") (pintype "passive"))
      (node (ref "T5") (pin "2") (pinfunction "E_2") (pintype "passive"))
      (node (ref "TP5") (pin "TP") (pinfunction "TP_TP") (pintype "input"))
      (node (ref "TP8") (pin "TP") (pinfunction "TP_TP") (pintype "input"))
      (node (ref "U1") (pin "GND") (pinfunction "GND_GND") (pintype "power_in"))
      (node (ref "U2") (pin "10") (pinfunction "GND_10") (pintype "power_in"))
      (node (ref "U2") (pin "14") (pinfunction "GND_14") (pintype "power_in"))
      (node (ref "U2") (pin "17") (pinfunction "GND_17") (pintype "power_in"))
      (node (ref "U2") (pin "24") (pinfunction "GND_24") (pintype "power_in"))
      (node (ref "U3") (pin "6") (pinfunction "VSS_6") (pintype "power_in"))
      (node (ref "U4") (pin "3") (pinfunction "GND_3") (pintype "power_in"))
      (node (ref "U4") (pin "6") (pinfunction "GND_6") (pintype "power_in"))
      (node (ref "U5") (pin "2") (pinfunction "GND_2") (pintype "power_in"))
      (node (ref "U6") (pin "2") (pinfunction "GND_2") (pintype "power_in"))
      (node (ref "U7") (pin "P$3") (pinfunction "GND_P$3") (pintype "bidirectional"))
      (node (ref "U9") (pin "3") (pinfunction "GND_3") (pintype "power_in"))
      (node (ref "X2") (pin "2") (pinfunction "KL_2") (pintype "passive"))
      (node (ref "X2") (pin "4") (pinfunction "KL_4") (pintype "passive"))
      (node (ref "X2") (pin "6") (pinfunction "KL_6") (pintype "passive"))
      (node (ref "X2") (pin "8") (pinfunction "KL_8") (pintype "passive"))
      (node (ref "X3") (pin "4") (pinfunction "KL_4") (pintype "passive"))
      (node (ref "X3") (pin "6") (pinfunction "KL_6") (pintype "passive"))
    )
    (net (code "18") (name "LIGHT_PWM") (class "Default")
      (node (ref "R5") (pin "1") (pinfunction "1_1") (pintype "passive"))
      (node (ref "U2") (pin "26") (pinfunction "GPIO2/TXD1_26") (pintype "bidirectional"))
    )
    (net (code "19") (name "LIGHT_SENSOR") (class "Default")
      (node (ref "R23") (pin "2") (pinfunction "2_2") (pintype "passive"))
      (node (ref "TP4") (pin "TP") (pinfunction "TP_TP") (pintype "input"))
      (node (ref "U2") (pin "1") (pinfunction "ADC0_1") (pintype "bidirectional"))
      (node (ref "U6") (pin "9") (pinfunction "A2_9") (pintype "input"))
      (node (ref "U8") (pin "2") (pinfunction "E_2") (pintype "passive"))
      (node (ref "U9") (pin "6") (pinfunction "AIN2_6") (pintype "input"))
    )
    (net (code "20") (name "MAIN_DOOR") (class "Default")
      (node (ref "R6") (pin "2") (pinfunction "2_2") (pintype "passive"))
      (node (ref "R7") (pin "1") (pinfunction "1_1") (pintype "passive"))
      (node (ref "U2") (pin "22") (pinfunction "GPIO12_22") (pintype "bidirectional"))
      (node (ref "X3") (pin "3") (pinfunction "KL_3") (pintype "passive"))
    )
    (net (code "21") (name "MOTOR_EN") (class "Default")
      (node (ref "IC2") (pin "2") (pinfunction "I_2") (pintype "input"))
      (node (ref "R38") (pin "1") (pinfunction "1_1") (pintype "passive"))
      (node (ref "U2") (pin "18") (pinfunction "GPIO1/TXD0_18") (pintype "bidirectional"))
    )
    (net (code "22") (name "MOTOR_PWM") (class "Default")
      (node (ref "IC1") (pin "2") (pinfunction "I_2") (pintype "input"))
      (node (ref "R37") (pin "1") (pinfunction "1_1") (pintype "passive"))
      (node (ref "TP6") (pin "TP") (pinfunction "TP_TP") (pintype "input"))
      (node (ref "U2") (pin "20") (pinfunction "GPIO15/TXD2_20") (pintype "bidirectional"))
      (node (ref "U3") (pin "4") (pinfunction "ALI_4") (pintype "bidirectional"))
    )
    (net (code "23") (name "NESTING_BOX") (class "Default")
      (node (ref "R8") (pin "2") (pinfunction "2_2") (pintype "passive"))
      (node (ref "R9") (pin "1") (pinfunction "1_1") (pintype "passive"))
      (node (ref "U2") (pin "21") (pinfunction "GPIO13/RXD2_21") (pintype "bidirectional"))
      (node (ref "X3") (pin "5") (pinfunction "KL_5") (pintype "passive"))
    )
    (net (code "24") (name "Net-(C1-+)") (class "Default")
      (node (ref "C1") (pin "POS") (pinfunction "+_POS") (pintype "passive"))
      (node (ref "C3") (pin "1") (pinfunction "1_1") (pintype "passive"))
      (node (ref "C5") (pin "1") (pinfunction "1_1") (pintype "passive"))
      (node (ref "F1") (pin "1") (pinfunction "1_1") (pintype "passive"))
      (node (ref "L1") (pin "2") (pinfunction "2_2") (pintype "passive"))
      (node (ref "U4") (pin "4") (pinfunction "FB_4") (pintype "power_in"))
    )
    (net (code "25") (name "Net-(C2-+)") (class "Default")
      (node (ref "C2") (pin "POS") (pinfunction "+_POS") (pintype "passive"))
      (node (ref "C4") (pin "1") (pinfunction "1_1") (pintype "passive"))
      (node (ref "L3") (pin "2") (pinfunction "2_2") (pintype "passive"))
      (node (ref "U4") (pin "1") (pinfunction "VIN_1") (pintype "power_in"))
    )
    (net (code "26") (name "Net-(D1-C)") (class "Default")
      (node (ref "D1") (pin "K") (pinfunction "C_K") (pintype "passive"))
      (node (ref "L1") (pin "1") (pinfunction "1_1") (pintype "passive"))
      (node (ref "U4") (pin "2") (pinfunction "SW_2") (pintype "power_in"))
    )
    (net (code "27") (name "Net-(D5-A)") (class "Default")
      (node (ref "C21") (pin "2") (pinfunction "2_2") (pintype "passive"))
      (node (ref "D5") (pin "1") (pinfunction "A_1") (pintype "passive"))
      (node (ref "Q6") (pin "G") (pinfunction "G_G") (pintype "passive"))
      (node (ref "R32") (pin "2") (pinfunction "2_2") (pintype "passive"))
    )
    (net (code "28") (name "Net-(F3-Pad1)") (class "Default")
      (node (ref "F3") (pin "1") (pinfunction "1_1") (pintype "passive"))
      (node (ref "L2") (pin "3") (pinfunction "3_3") (pintype "passive"))
    )
    (net (code "29") (name "Net-(IC1A-O)") (class "Default")
      (node (ref "IC1") (pin "4") (pinfunction "O_4") (pintype "open_collector"))
      (node (ref "R44") (pin "1") (pinfunction "1_1") (pintype "passive"))
      (node (ref "TP7") (pin "TP") (pinfunction "TP_TP") (pintype "input"))
      (node (ref "U3") (pin "3") (pinfunction "BLI_3") (pintype "bidirectional"))
    )
    (net (code "30") (name "Net-(IC2A-O)") (class "Default")
      (node (ref "IC2") (pin "4") (pinfunction "O_4") (pintype "open_collector"))
      (node (ref "R45") (pin "1") (pinfunction "1_1") (pintype "passive"))
      (node (ref "U3") (pin "8") (pinfunction "DIS_8") (pintype "bidirectional"))
    )
    (net (code "31") (name "Net-(K1-Pad2)") (class "Default")
      (node (ref "K1") (pin "2") (pinfunction "2_2") (pintype "bidirectional"))
      (node (ref "K1") (pin "5") (pinfunction "5_5") (pintype "bidirectional"))
      (node (ref "K2") (pin "4") (pinfunction "4_4") (pintype "bidirectional"))
      (node (ref "K2") (pin "5") (pinfunction "5_5") (pintype "bidirectional"))
    )
    (net (code "32") (name "Net-(K1-Pad4)") (class "Default")
      (node (ref "K1") (pin "4") (pinfunction "4_4") (pintype "bidirectional"))
      (node (ref "R35") (pin "2") (pinfunction "2_2") (pintype "passive"))
      (node (ref "R36") (pin "1") (pinfunction "1_1") (pintype "passive"))
    )
    (net (code "33") (name "Net-(K1-Pad7)") (class "Default")
      (node (ref "K1") (pin "7") (pinfunction "7_7") (pintype "bidirectional"))
      (node (ref "R33") (pin "2") (pinfunction "2_2") (pintype "passive"))
      (node (ref "R34") (pin "2") (pinfunction "2_2") (pintype "passive"))
    )
    (net (code "34") (name "Net-(LED1-PadC)") (class "Default")
      (node (ref "LED1") (pin "C") (pinfunction "C_C") (pintype "passive"))
      (node (ref "R29") (pin "2") (pinfunction "2_2") (pintype "passive"))
    )
    (net (code "35") (name "Net-(LED2-PadC)") (class "Default")
      (node (ref "LED2") (pin "C") (pinfunction "C_C") (pintype "passive"))
      (node (ref "R30") (pin "2") (pinfunction "2_2") (pintype "passive"))
    )
    (net (code "36") (name "Net-(LED3-PadC)") (class "Default")
      (node (ref "LED3") (pin "C") (pinfunction "C_C") (pintype "passive"))
      (node (ref "R31") (pin "2") (pinfunction "2_2") (pintype "passive"))
    )
    (net (code "37") (name "Net-(Q1-D)") (class "Default")
      (node (ref "Q1") (pin "3") (pinfunction "D_3") (pintype "passive"))
      (node (ref "X4") (pin "2") (pinfunction "KL_2") (pintype "passive"))
    )
    (net (code "38") (name "Net-(Q1-G)") (class "Default")
      (node (ref "Q1") (pin "1") (pinfunction "G_1") (pintype "passive"))
      (node (ref "R1") (pin "2") (pinfunction "2_2") (pintype "passive"))
      (node (ref "TP9") (pin "TP") (pinfunction "TP_TP") (pintype "input"))
    )
    (net (code "39") (name "Net-(Q2-G)") (class "Default")
      (node (ref "Q2") (pin "1") (pinfunction "G_1") (pintype "passive"))
      (node (ref "R40") (pin "2") (pinfunction "2_2") (pintype "passive"))
    )
    (net (code "40") (name "Net-(Q3-G)") (class "Default")
      (node (ref "Q3") (pin "1") (pinfunction "G_1") (pintype "passive"))
      (node (ref "R42") (pin "2") (pinfunction "2_2") (pintype "passive"))
    )
    (net (code "41") (name "Net-(Q3-S)") (class "Default")
      (node (ref "Q3") (pin "2") (pinfunction "S_2") (pintype "passive"))
      (node (ref "R25") (pin "2") (pinfunction "2_2") (pintype "passive"))
      (node (ref "R26") (pin "2") (pinfunction "2_2") (pintype "passive"))
    )
    (net (code "42") (name "Net-(Q4-G)") (class "Default")
      (node (ref "Q4") (pin "1") (pinfunction "G_1") (pintype "passive"))
      (node (ref "R41") (pin "1") (pinfunction "1_1") (pintype "passive"))
    )
    (net (code "43") (name "Net-(Q5-G)") (class "Default")
      (node (ref "Q5") (pin "1") (pinfunction "G_1") (pintype "passive"))
      (node (ref "R43") (pin "1") (pinfunction "1_1") (pintype "passive"))
    )
    (net (code "44") (name "Net-(Q5-S)") (class "Default")
      (node (ref "Q5") (pin "2") (pinfunction "S_2") (pintype "passive"))
      (node (ref "R27") (pin "2") (pinfunction "2_2") (pintype "passive"))
      (node (ref "R28") (pin "1") (pinfunction "1_1") (pintype "passive"))
    )
    (net (code "45") (name "Net-(T1-B)") (class "Default")
      (node (ref "R5") (pin "2") (pinfunction "2_2") (pintype "passive"))
      (node (ref "T1") (pin "1") (pinfunction "B_1") (pintype "passive"))
      (node (ref "TP10") (pin "TP") (pinfunction "TP_TP") (pintype "input"))
    )
    (net (code "46") (name "Net-(T1-C)") (class "Default")
      (node (ref "R2") (pin "1") (pinfunction "1_1") (pintype "passive"))
      (node (ref "R4") (pin "1") (pinfunction "1_1") (pintype "passive"))
      (node (ref "T1") (pin "3") (pinfunction "C_3") (pintype "passive"))
    )
    (net (code "47") (name "Net-(T2-B)") (class "Default")
      (node (ref "R4") (pin "2") (pinfunction "2_2") (pintype "passive"))
      (node (ref "T2") (pin "1") (pinfunction "B_1") (pintype "passive"))
      (node (ref "T3") (pin "B") (pinfunction "B_B") (pintype "passive"))
    )
    (net (code "48") (name "Net-(T2-E)") (class "Default")
      (node (ref "R1") (pin "1") (pinfunction "1_1") (pintype "passive"))
      (node (ref "T2") (pin "2") (pinfunction "E_2") (pintype "passive"))
      (node (ref "T3") (pin "E") (pinfunction "E_E") (pintype "passive"))
    )
    (net (code "49") (name "Net-(T4-B)") (class "Default")
      (node (ref "R37") (pin "2") (pinfunction "2_2") (pintype "passive"))
      (node (ref "T4") (pin "1") (pinfunction "B_1") (pintype "passive"))
    )
    (net (code "50") (name "Net-(T4-C)") (class "Default")
      (node (ref "D6") (pin "A") (pinfunction "A_A") (pintype "passive"))
      (node (ref "K1") (pin "8") (pinfunction "8_8") (pintype "bidirectional"))
      (node (ref "T4") (pin "3") (pinfunction "C_3") (pintype "passive"))
    )
    (net (code "51") (name "Net-(T5-B)") (class "Default")
      (node (ref "R38") (pin "2") (pinfunction "2_2") (pintype "passive"))
      (node (ref "T5") (pin "1") (pinfunction "B_1") (pintype "passive"))
    )
    (net (code "52") (name "Net-(T5-C)") (class "Default")
      (node (ref "D7") (pin "A") (pinfunction "A_A") (pintype "passive"))
      (node (ref "K2") (pin "8") (pinfunction "8_8") (pintype "bidirectional"))
      (node (ref "T5") (pin "3") (pinfunction "C_3") (pintype "passive"))
    )
    (net (code "53") (name "Net-(U3-AHB)") (class "Default")
      (node (ref "C15") (pin "1") (pinfunction "1_1") (pintype "passive"))
      (node (ref "D3") (pin "C") (pinfunction "C_C") (pintype "passive"))
      (node (ref "U3") (pin "9") (pinfunction "AHB_9") (pintype "bidirectional"))
    )
    (net (code "54") (name "Net-(U3-BHB)") (class "Default")
      (node (ref "C14") (pin "2") (pinfunction "2_2") (pintype "passive"))
      (node (ref "D2") (pin "C") (pinfunction "C_C") (pintype "passive"))
      (node (ref "U3") (pin "1") (pinfunction "BHB_1") (pintype "bidirectional"))
    )
    (net (code "55") (name "Net-(U3-DEL)") (class "Default")
      (node (ref "R24") (pin "2") (pinfunction "2_2") (pintype "passive"))
      (node (ref "U3") (pin "5") (pinfunction "DEL_5") (pintype "bidirectional"))
    )
    (net (code "56") (name "Net-(U4-SHDN)") (class "Default")
      (node (ref "R16") (pin "2") (pinfunction "2_2") (pintype "passive"))
      (node (ref "U4") (pin "5") (pinfunction "SHDN_5") (pintype "input"))
    )
    (net (code "57") (name "Net-(U5-ON{slash}_OFF)") (class "Default")
      (node (ref "R18") (pin "2") (pinfunction "2_2") (pintype "passive"))
      (node (ref "U5") (pin "3") (pinfunction "ON/_OFF_3") (pintype "input"))
    )
    (net (code "58") (name "Net-(U6-A3)") (class "Default")
      (node (ref "TP2") (pin "TP") (pinfunction "TP_TP") (pintype "input"))
      (node (ref "U6") (pin "10") (pinfunction "A3_10") (pintype "input"))
    )
    (net (code "59") (name "Net-(U6-ADDR)") (class "Default")
      (node (ref "R19") (pin "2") (pinfunction "2_2") (pintype "passive"))
      (node (ref "U6") (pin "5") (pinfunction "ADDR_5") (pintype "input"))
    )
    (net (code "60") (name "Net-(U7-VDD)") (class "Default")
      (node (ref "C12") (pin "1") (pinfunction "1_1") (pintype "passive"))
      (node (ref "C13") (pin "1") (pinfunction "1_1") (pintype "passive"))
      (node (ref "R22") (pin "2") (pinfunction "2_2") (pintype "passive"))
      (node (ref "U7") (pin "P$2") (pinfunction "VDD_P$2") (pintype "power_in"))
    )
    (net (code "61") (name "Net-(U9-ADDR)") (class "Default")
      (node (ref "R39") (pin "1") (pinfunction "1_1") (pintype "passive"))
      (node (ref "U9") (pin "1") (pinfunction "ADDR_1") (pintype "input"))
    )
    (net (code "62") (name "Net-(U9-AIN3)") (class "Default")
      (node (ref "TP13") (pin "TP") (pinfunction "TP_TP") (pintype "input"))
      (node (ref "U9") (pin "7") (pinfunction "AIN3_7") (pintype "input"))
    )
    (net (code "63") (name "Net-(U9-ALERT)") (class "Default")
      (node (ref "TP12") (pin "TP") (pinfunction "TP_TP") (pintype "input"))
      (node (ref "U9") (pin "2") (pinfunction "ALERT_2") (pintype "output"))
    )
    (net (code "64") (name "Net-(X1A-KL)") (class "Default")
      (node (ref "L2") (pin "1") (pinfunction "1_1") (pintype "passive"))
      (node (ref "X1") (pin "1") (pinfunction "KL_1") (pintype "passive"))
    )
    (net (code "65") (name "Net-(X1B-KL)") (class "Default")
      (node (ref "L2") (pin "2") (pinfunction "2_2") (pintype "passive"))
      (node (ref "X1") (pin "2") (pinfunction "KL_2") (pintype "passive"))
    )
    (net (code "66") (name "Net-(X4E-KL)") (class "Default")
      (node (ref "K1") (pin "3") (pinfunction "3_3") (pintype "bidirectional"))
      (node (ref "X4") (pin "5") (pinfunction "KL_5") (pintype "passive"))
    )
    (net (code "67") (name "Net-(X4F-KL)") (class "Default")
      (node (ref "K1") (pin "6") (pinfunction "6_6") (pintype "bidirectional"))
      (node (ref "X4") (pin "6") (pinfunction "KL_6") (pintype "passive"))
    )
    (net (code "68") (name "SCL") (class "Default")
      (node (ref "R20") (pin "1") (pinfunction "1_1") (pintype "passive"))
      (node (ref "U2") (pin "29") (pinfunction "GPIO5_29") (pintype "bidirectional"))
      (node (ref "U6") (pin "3") (pinfunction "SCL_3") (pintype "bidirectional"))
      (node (ref "U7") (pin "P$1") (pinfunction "SCL_P$1") (pintype "bidirectional"))
      (node (ref "U9") (pin "10") (pinfunction "SCL_10") (pintype "bidirectional"))
    )
    (net (code "69") (name "SDA") (class "Default")
      (node (ref "R21") (pin "1") (pinfunction "1_1") (pintype "passive"))
      (node (ref "U2") (pin "28") (pinfunction "GPIO4_28") (pintype "bidirectional"))
      (node (ref "U6") (pin "4") (pinfunction "SDA_4") (pintype "bidirectional"))
      (node (ref "U7") (pin "P$4") (pinfunction "SDA_P$4") (pintype "bidirectional"))
      (node (ref "U9") (pin "9") (pinfunction "SDA_9") (pintype "bidirectional"))
    )
    (net (code "70") (name "unconnected-(K2-Pad2)") (class "Default")
      (node (ref "K2") (pin "2") (pinfunction "2_2") (pintype "bidirectional"))
    )
    (net (code "71") (name "unconnected-(K2-Pad7)") (class "Default")
      (node (ref "K2") (pin "7") (pinfunction "7_7") (pintype "bidirectional"))
    )
    (net (code "72") (name "unconnected-(U1-PadNULL)") (class "Default")
      (node (ref "U1") (pin "NULL") (pinfunction "NULL_NULL") (pintype "no_connect"))
    )
    (net (code "73") (name "unconnected-(U2-CS{slash}SDCMD-Pad7)") (class "Default")
      (node (ref "U2") (pin "7") (pinfunction "CS/SDCMD_7") (pintype "bidirectional"))
    )
    (net (code "74") (name "unconnected-(U2-EN-Pad12)") (class "Default")
      (node (ref "U2") (pin "12") (pinfunction "EN_12") (pintype "bidirectional"))
    )
    (net (code "75") (name "unconnected-(U2-GPIO9{slash}SDD2-Pad5)") (class "Default")
      (node (ref "U2") (pin "5") (pinfunction "GPIO9/SDD2_5") (pintype "bidirectional"))
    )
    (net (code "76") (name "unconnected-(U2-GPIO10{slash}SDD3-Pad4)") (class "Default")
      (node (ref "U2") (pin "4") (pinfunction "GPIO10/SDD3_4") (pintype "bidirectional"))
    )
    (net (code "77") (name "unconnected-(U2-MISO{slash}SDD0-Pad8)") (class "Default")
      (node (ref "U2") (pin "8") (pinfunction "MISO/SDD0_8") (pintype "bidirectional"))
    )
    (net (code "78") (name "unconnected-(U2-MOSI{slash}SDD1-Pad6)") (class "Default")
      (node (ref "U2") (pin "6") (pinfunction "MOSI/SDD1_6") (pintype "bidirectional"))
    )
    (net (code "79") (name "unconnected-(U2-RST-Pad13)") (class "Default")
      (node (ref "U2") (pin "13") (pinfunction "RST_13") (pintype "bidirectional"))
    )
    (net (code "80") (name "unconnected-(U2-RSV0-Pad2)") (class "Default")
      (node (ref "U2") (pin "2") (pinfunction "RSV0_2") (pintype "no_connect"))
    )
    (net (code "81") (name "unconnected-(U2-RSV1-Pad3)") (class "Default")
      (node (ref "U2") (pin "3") (pinfunction "RSV1_3") (pintype "no_connect"))
    )
    (net (code "82") (name "unconnected-(U2-SCLK{slash}SDCLK-Pad9)") (class "Default")
      (node (ref "U2") (pin "9") (pinfunction "SCLK/SDCLK_9") (pintype "bidirectional"))
    )
    (net (code "83") (name "unconnected-(U5-NC-Pad4)") (class "Default")
      (node (ref "U5") (pin "4") (pinfunction "NC_4") (pintype "no_connect"))
    )
    (net (code "84") (name "unconnected-(U6-ALRT-Pad6)") (class "Default")
      (node (ref "U6") (pin "6") (pinfunction "ALRT_6") (pintype "output"))
    )
  )
)
